# JHDH-8412_powerbank.net
KiCad netlist of a schematic drawn in Altium Designer
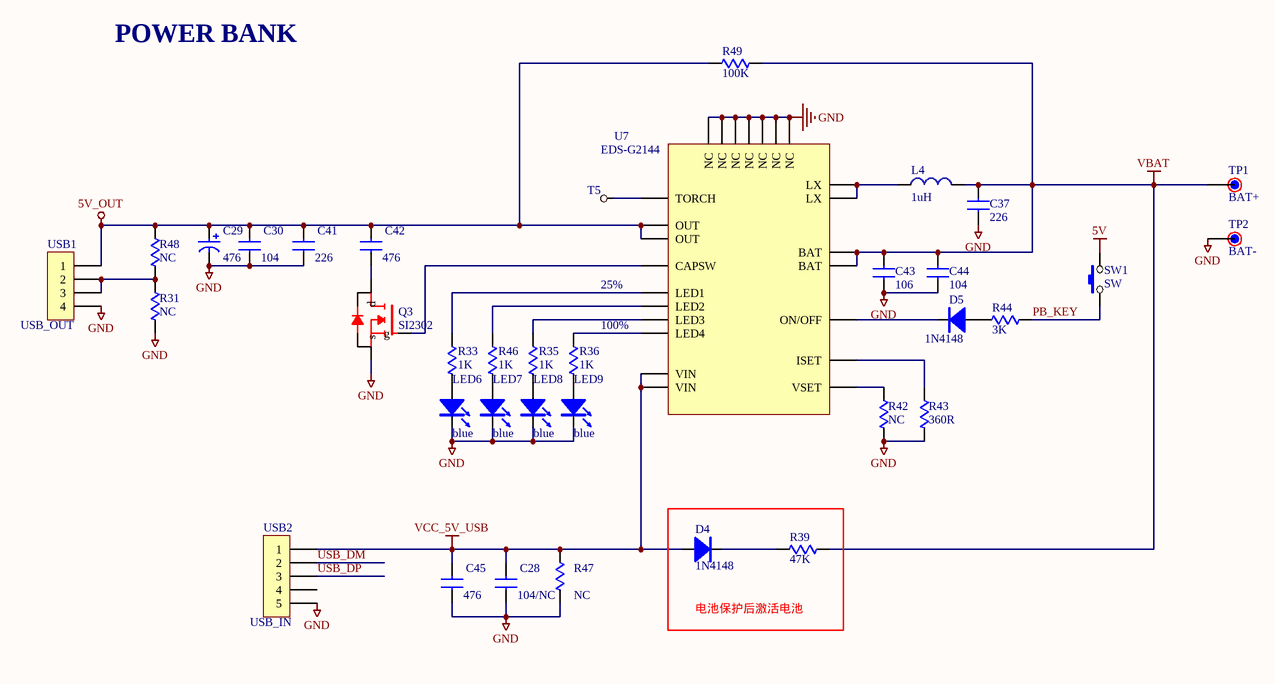
[diagram p0: JHDH-8412_powerbank.SchDoc]

(export (version "E")
  (design (tool "Eeschema 10.0.6"))
  (components
    (comp (ref "C28")
      (value "104/NC")
      (footprint "C0402")
      (description "Capacitor")
      (libsource (lib "*") (part "CAP"))
    )
    (comp (ref "C29")
      (value "476")
      (footprint "C1206")
      (description "电解电容")
      (libsource (lib "SCH") (part "CAP1"))
    )
    (comp (ref "C30")
      (value "104")
      (footprint "C0402")
      (description "Capacitor")
      (libsource (lib "*") (part "CAP"))
    )
    (comp (ref "C37")
      (value "226")
      (footprint "C0805")
      (description "Capacitor")
      (libsource (lib "*") (part "CAP"))
    )
    (comp (ref "C41")
      (value "226")
      (footprint "C0805")
      (description "Capacitor")
      (libsource (lib "*") (part "CAP"))
    )
    (comp (ref "C42")
      (value "476")
      (footprint "C0805")
      (description "Capacitor")
      (libsource (lib "*") (part "CAP"))
    )
    (comp (ref "C43")
      (value "106")
      (footprint "C0805")
      (description "Capacitor")
      (libsource (lib "*") (part "CAP"))
    )
    (comp (ref "C44")
      (value "104")
      (footprint "C0402")
      (description "Capacitor")
      (libsource (lib "*") (part "CAP"))
    )
    (comp (ref "C45")
      (value "476")
      (footprint "C0805")
      (description "Capacitor")
      (libsource (lib "*") (part "CAP"))
    )
    (comp (ref "D4")
      (value "1N4148")
      (footprint "D1206")
      (description "玻璃二极管")
      (libsource (lib "*") (part "1N4148"))
    )
    (comp (ref "D5")
      (value "1N4148")
      (footprint "D1206")
      (description "玻璃二极管")
      (libsource (lib "*") (part "1N4148"))
    )
    (comp (ref "L4") (value "1uH") (footprint "CD75") (description "电感") (libsource (lib "*") (part "L-1")))
    (comp (ref "LED6")
      (value "blue")
      (footprint "LED0603B")
      (description "LED/蓝色")
      (libsource (lib "SCH") (part "LED-B"))
    )
    (comp (ref "LED7")
      (value "blue")
      (footprint "LED0603B")
      (description "LED/蓝色")
      (libsource (lib "SCH") (part "LED-B"))
    )
    (comp (ref "LED8")
      (value "blue")
      (footprint "LED0603B")
      (description "LED/蓝色")
      (libsource (lib "SCH") (part "LED-B"))
    )
    (comp (ref "LED9")
      (value "blue")
      (footprint "LED0603B")
      (description "LED/蓝色")
      (libsource (lib "SCH") (part "LED-B"))
    )
    (comp (ref "Q3")
      (value "SI2302")
      (footprint "SOT23")
      (description "Mosfet/N")
      (libsource (lib "*") (part "MOSFETN"))
    )
    (comp (ref "R31")
      (value "NC")
      (footprint "R0402")
      (description "Resistor")
      (libsource (lib "*") (part "RES"))
    )
    (comp (ref "R33")
      (value "1K")
      (footprint "R0402")
      (description "Resistor")
      (libsource (lib "*") (part "RES"))
    )
    (comp (ref "R35")
      (value "1K")
      (footprint "R0402")
      (description "Resistor")
      (libsource (lib "*") (part "RES"))
    )
    (comp (ref "R36")
      (value "1K")
      (footprint "R0402")
      (description "Resistor")
      (libsource (lib "*") (part "RES"))
    )
    (comp (ref "R39")
      (value "47K")
      (footprint "R0402")
      (description "Resistor")
      (libsource (lib "*") (part "RES"))
    )
    (comp (ref "R42")
      (value "NC")
      (footprint "R0402")
      (description "Resistor")
      (libsource (lib "*") (part "RES"))
    )
    (comp (ref "R43")
      (value "360R")
      (footprint "R0402")
      (description "Resistor")
      (libsource (lib "*") (part "RES"))
    )
    (comp (ref "R44")
      (value "3K")
      (footprint "R0402")
      (description "Resistor")
      (libsource (lib "*") (part "RES"))
    )
    (comp (ref "R46")
      (value "1K")
      (footprint "R0402")
      (description "Resistor")
      (libsource (lib "*") (part "RES"))
    )
    (comp (ref "R47")
      (value "NC")
      (footprint "R0402")
      (description "Resistor")
      (libsource (lib "*") (part "RES"))
    )
    (comp (ref "R48")
      (value "NC")
      (footprint "R0402")
      (description "Resistor")
      (libsource (lib "*") (part "RES"))
    )
    (comp (ref "R49")
      (value "100K")
      (footprint "R0402")
      (description "Resistor")
      (libsource (lib "*") (part "RES"))
    )
    (comp (ref "SW1")
      (value "SW")
      (footprint "KEY/IT-1201")
      (description "Tact Switch")
      (libsource (lib "SCH") (part "SW"))
    )
    (comp (ref "T5") (value "~") (footprint "PAD0") (description "Test") (libsource (lib "*") (part "CON1")))
    (comp (ref "TP1") (value "BAT+") (footprint "LCH:PAD0") (libsource (lib "SCH") (part "TP")))
    (comp (ref "TP2") (value "BAT-") (footprint "LCH:PAD0") (libsource (lib "SCH") (part "TP")))
    (comp (ref "U7") (value "EDS-G2144") (footprint "TQFN24-4*4") (libsource (lib "*") (part "Component_1")))
    (comp (ref "USB1")
      (value "USB_OUT")
      (footprint "USB-A-SMT")
      (description "Connector")
      (libsource (lib "*") (part "CON4"))
    )
    (comp (ref "USB2")
      (value "USB_IN")
      (footprint "USB-009")
      (description "Connector")
      (libsource (lib "*") (part "CON5"))
    )
  )
  (nets
    (net (code "1") (name "/PB_KEY") (class "Default")
      (node (ref "R44") (pin "2") (pinfunction "2_2") (pintype "passive"))
      (node (ref "SW1") (pin "1") (pinfunction "1_1") (pintype "passive"))
    )
    (net (code "2") (name "/USB_DM") (class "Default")
      (node (ref "USB2") (pin "2") (pinfunction "2_2") (pintype "passive"))
    )
    (net (code "3") (name "/USB_DP") (class "Default")
      (node (ref "USB2") (pin "3") (pinfunction "3_3") (pintype "passive"))
    )
    (net (code "4") (name "5V") (class "Default")
      (node (ref "SW1") (pin "2") (pinfunction "2_2") (pintype "passive"))
    )
    (net (code "5") (name "5V_OUT") (class "Default")
      (node (ref "C29") (pin "1") (pinfunction "1_1") (pintype "passive"))
      (node (ref "C30") (pin "1") (pinfunction "1_1") (pintype "passive"))
      (node (ref "C41") (pin "1") (pinfunction "1_1") (pintype "passive"))
      (node (ref "C42") (pin "1") (pinfunction "1_1") (pintype "passive"))
      (node (ref "R48") (pin "1") (pinfunction "1_1") (pintype "passive"))
      (node (ref "R49") (pin "1") (pinfunction "1_1") (pintype "passive"))
      (node (ref "U7") (pin "1") (pinfunction "OUT_1") (pintype "passive"))
      (node (ref "U7") (pin "2") (pinfunction "OUT_2") (pintype "passive"))
      (node (ref "USB1") (pin "1") (pinfunction "1_1") (pintype "passive"))
    )
    (net (code "6") (name "GND") (class "Default")
      (node (ref "C28") (pin "2") (pinfunction "2_2") (pintype "passive"))
      (node (ref "C29") (pin "2") (pinfunction "2_2") (pintype "passive"))
      (node (ref "C30") (pin "2") (pinfunction "2_2") (pintype "passive"))
      (node (ref "C37") (pin "2") (pinfunction "2_2") (pintype "passive"))
      (node (ref "C41") (pin "2") (pinfunction "2_2") (pintype "passive"))
      (node (ref "C43") (pin "2") (pinfunction "2_2") (pintype "passive"))
      (node (ref "C44") (pin "2") (pinfunction "2_2") (pintype "passive"))
      (node (ref "C45") (pin "2") (pinfunction "2_2") (pintype "passive"))
      (node (ref "LED6") (pin "2") (pinfunction "K_2") (pintype "passive"))
      (node (ref "LED7") (pin "2") (pinfunction "K_2") (pintype "passive"))
      (node (ref "LED8") (pin "2") (pinfunction "K_2") (pintype "passive"))
      (node (ref "LED9") (pin "2") (pinfunction "K_2") (pintype "passive"))
      (node (ref "Q3") (pin "2") (pinfunction "s_2") (pintype "passive"))
      (node (ref "R31") (pin "2") (pinfunction "2_2") (pintype "passive"))
      (node (ref "R42") (pin "2") (pinfunction "2_2") (pintype "passive"))
      (node (ref "R43") (pin "2") (pinfunction "2_2") (pintype "passive"))
      (node (ref "R47") (pin "2") (pinfunction "2_2") (pintype "passive"))
      (node (ref "TP2") (pin "1") (pinfunction "1_1") (pintype "passive"))
      (node (ref "U7") (pin "10") (pinfunction "NC_10") (pintype "passive"))
      (node (ref "U7") (pin "19") (pinfunction "NC_19") (pintype "passive"))
      (node (ref "U7") (pin "20") (pinfunction "NC_20") (pintype "passive"))
      (node (ref "U7") (pin "21") (pinfunction "NC_21") (pintype "passive"))
      (node (ref "U7") (pin "22") (pinfunction "NC_22") (pintype "passive"))
      (node (ref "U7") (pin "23") (pinfunction "NC_23") (pintype "passive"))
      (node (ref "U7") (pin "24") (pinfunction "NC_24") (pintype "passive"))
      (node (ref "USB1") (pin "4") (pinfunction "4_4") (pintype "passive"))
      (node (ref "USB2") (pin "5") (pinfunction "5_5") (pintype "passive"))
    )
    (net (code "7") (name "Net-(D4-K)") (class "Default")
      (node (ref "D4") (pin "2") (pinfunction "K_2") (pintype "passive"))
      (node (ref "R39") (pin "1") (pinfunction "1_1") (pintype "passive"))
    )
    (net (code "8") (name "Net-(D5-A)") (class "Default")
      (node (ref "D5") (pin "1") (pinfunction "A_1") (pintype "passive"))
      (node (ref "R44") (pin "1") (pinfunction "1_1") (pintype "passive"))
    )
    (net (code "9") (name "Net-(D5-K)") (class "Default")
      (node (ref "D5") (pin "2") (pinfunction "K_2") (pintype "passive"))
      (node (ref "U7") (pin "16") (pinfunction "ON/OFF_16") (pintype "passive"))
    )
    (net (code "10") (name "Net-(L4-Pad1)") (class "Default")
      (node (ref "L4") (pin "1") (pinfunction "1_1") (pintype "passive"))
      (node (ref "U7") (pin "17") (pinfunction "LX_17") (pintype "passive"))
      (node (ref "U7") (pin "18") (pinfunction "LX_18") (pintype "passive"))
    )
    (net (code "11") (name "Net-(LED6-A)") (class "Default")
      (node (ref "LED6") (pin "1") (pinfunction "A_1") (pintype "passive"))
      (node (ref "R33") (pin "1") (pinfunction "1_1") (pintype "passive"))
    )
    (net (code "12") (name "Net-(LED7-A)") (class "Default")
      (node (ref "LED7") (pin "1") (pinfunction "A_1") (pintype "passive"))
      (node (ref "R46") (pin "1") (pinfunction "1_1") (pintype "passive"))
    )
    (net (code "13") (name "Net-(LED8-A)") (class "Default")
      (node (ref "LED8") (pin "1") (pinfunction "A_1") (pintype "passive"))
      (node (ref "R35") (pin "1") (pinfunction "1_1") (pintype "passive"))
    )
    (net (code "14") (name "Net-(LED9-A)") (class "Default")
      (node (ref "LED9") (pin "1") (pinfunction "A_1") (pintype "passive"))
      (node (ref "R36") (pin "1") (pinfunction "1_1") (pintype "passive"))
    )
    (net (code "15") (name "Net-(Q3-d)") (class "Default")
      (node (ref "C42") (pin "2") (pinfunction "2_2") (pintype "passive"))
      (node (ref "Q3") (pin "3") (pinfunction "d_3") (pintype "passive"))
    )
    (net (code "16") (name "Net-(Q3-g)") (class "Default")
      (node (ref "Q3") (pin "1") (pinfunction "g_1") (pintype "passive"))
      (node (ref "U7") (pin "3") (pinfunction "CAPSW_3") (pintype "passive"))
    )
    (net (code "17") (name "Net-(R31-Pad1)") (class "Default")
      (node (ref "R31") (pin "1") (pinfunction "1_1") (pintype "passive"))
      (node (ref "R48") (pin "2") (pinfunction "2_2") (pintype "passive"))
      (node (ref "USB1") (pin "2") (pinfunction "2_2") (pintype "passive"))
      (node (ref "USB1") (pin "3") (pinfunction "3_3") (pintype "passive"))
    )
    (net (code "18") (name "Net-(T5-T)") (class "Default")
      (node (ref "T5") (pin "1") (pinfunction "T_1") (pintype "passive"))
      (node (ref "U7") (pin "12") (pinfunction "TORCH_12") (pintype "passive"))
    )
    (net (code "19") (name "Net-(U7-ISET)") (class "Default")
      (node (ref "R43") (pin "1") (pinfunction "1_1") (pintype "passive"))
      (node (ref "U7") (pin "15") (pinfunction "ISET_15") (pintype "passive"))
    )
    (net (code "20") (name "Net-(U7-LED1)") (class "Default")
      (node (ref "R33") (pin "2") (pinfunction "2_2") (pintype "passive"))
      (node (ref "U7") (pin "4") (pinfunction "LED1_4") (pintype "passive"))
    )
    (net (code "21") (name "Net-(U7-LED2)") (class "Default")
      (node (ref "R46") (pin "2") (pinfunction "2_2") (pintype "passive"))
      (node (ref "U7") (pin "5") (pinfunction "LED2_5") (pintype "passive"))
    )
    (net (code "22") (name "Net-(U7-LED3)") (class "Default")
      (node (ref "R35") (pin "2") (pinfunction "2_2") (pintype "passive"))
      (node (ref "U7") (pin "14") (pinfunction "LED3_14") (pintype "passive"))
    )
    (net (code "23") (name "Net-(U7-LED4)") (class "Default")
      (node (ref "R36") (pin "2") (pinfunction "2_2") (pintype "passive"))
      (node (ref "U7") (pin "13") (pinfunction "LED4_13") (pintype "passive"))
    )
    (net (code "24") (name "Net-(U7-VSET)") (class "Default")
      (node (ref "R42") (pin "1") (pinfunction "1_1") (pintype "passive"))
      (node (ref "U7") (pin "9") (pinfunction "VSET_9") (pintype "passive"))
    )
    (net (code "25") (name "VBAT") (class "Default")
      (node (ref "C37") (pin "1") (pinfunction "1_1") (pintype "passive"))
      (node (ref "C43") (pin "1") (pinfunction "1_1") (pintype "passive"))
      (node (ref "C44") (pin "1") (pinfunction "1_1") (pintype "passive"))
      (node (ref "L4") (pin "2") (pinfunction "2_2") (pintype "passive"))
      (node (ref "R39") (pin "2") (pinfunction "2_2") (pintype "passive"))
      (node (ref "R49") (pin "2") (pinfunction "2_2") (pintype "passive"))
      (node (ref "TP1") (pin "1") (pinfunction "1_1") (pintype "passive"))
      (node (ref "U7") (pin "11") (pinfunction "BAT_11") (pintype "passive"))
      (node (ref "U7") (pin "8") (pinfunction "BAT_8") (pintype "passive"))
    )
    (net (code "26") (name "VCC_5V_USB") (class "Default")
      (node (ref "C28") (pin "1") (pinfunction "1_1") (pintype "passive"))
      (node (ref "C45") (pin "1") (pinfunction "1_1") (pintype "passive"))
      (node (ref "D4") (pin "1") (pinfunction "A_1") (pintype "passive"))
      (node (ref "R47") (pin "1") (pinfunction "1_1") (pintype "passive"))
      (node (ref "U7") (pin "6") (pinfunction "VIN_6") (pintype "passive"))
      (node (ref "U7") (pin "7") (pinfunction "VIN_7") (pintype "passive"))
      (node (ref "USB2") (pin "1") (pinfunction "1_1") (pintype "passive"))
    )
    (net (code "27") (name "unconnected-(USB2-Pad4)") (class "Default")
      (node (ref "USB2") (pin "4") (pinfunction "4_4") (pintype "passive"))
    )
  )
)
